# Sheet1.net
KiCad netlist of a schematic drawn in Altium Designer
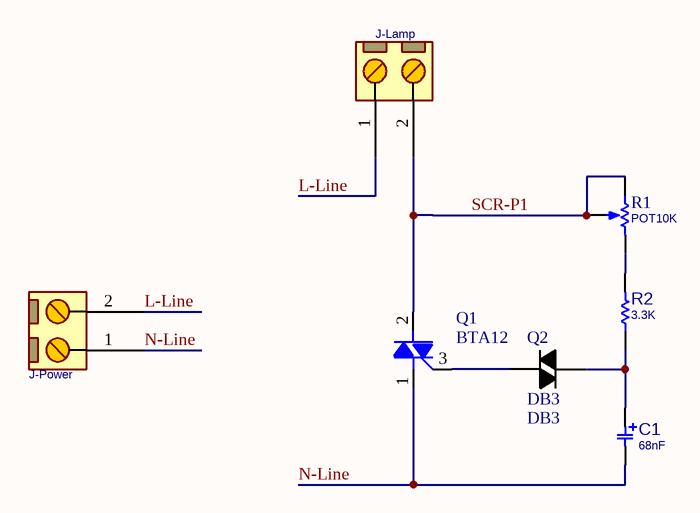
[diagram p0: Sheet1.SchDoc]

(export (version "E")
  (design (tool "Eeschema 10.0.6"))
  (components
    (comp (ref "C1")
      (value "68nF")
      (footprint "C_FLM_7X5H11")
      (description "CAP, THD, FILM,")
      (fields (field (name "MANF_P#") "MANF_PART#") (field (name "MANF") "MANF"))
      (libsource (lib "passive_thd") (part "CAP_THD_FLM"))
    )
    (comp (ref "J-Lamp")
      (value "CONN_TB2")
      (footprint "MSTB_2")
      (description "CONN, PHOENIX MSTB, 5-G, 5.08mm pitch")
      (libsource (lib "conn_terminalB") (part "CONN_MSTB_2"))
    )
    (comp (ref "J-Power")
      (value "CONN_TB2")
      (footprint "MSTB_2")
      (description "CONN, PHOENIX MSTB, 5-G, 5.08mm pitch")
      (libsource (lib "") (part "CONN_MSTB_2_1"))
    )
    (comp (ref "Q1")
      (value "BTA12")
      (footprint "TO220_3")
      (description "Triac, 600V, 12A, TO-220")
      (fields (field (name "MANF_P#") "BTA12-600BW, BTA12-600CW, BTA12-600TW") (field (name "MANF") "ST"))
      (libsource (lib "triac_diac") (part "TRIAC_BTA12-600_TO220"))
    )
    (comp (ref "Q2")
      (value "DB3")
      (footprint "D_AX03_DO35")
      (description "Diac, 32VBO, DO-35")
      (fields (field (name "MANF") "ST") (field (name "ALTIUM_VALUE") "DB3"))
      (libsource (lib "triac_diac") (part "DIAC_DB3_DO35"))
    )
    (comp (ref "R1")
      (value "POT10K")
      (footprint "VOL_R")
      (description "RESISTOR, THD, Potentiometer Volume")
      (libsource (lib "resistor_pot_trimmer") (part "RES_THD_POT_VOL"))
    )
    (comp (ref "R2")
      (value "3.3K")
      (footprint "R025W_AX04")
      (description "RESISTOR, THD")
      (fields (field (name "MANF_P#") "RK73H1ETTP4701F") (field (name "MANF") "KOA SPEER"))
      (libsource (lib "passive_thd") (part "RES_THD"))
    )
  )
  (nets
    (net (code "1") (name "/L-Line") (class "Default")
      (node (ref "J-Lamp") (pin "1") (pinfunction "1_1") (pintype "passive"))
      (node (ref "J-Power") (pin "2") (pinfunction "2_2") (pintype "passive"))
    )
    (net (code "2") (name "/N-Line") (class "Default")
      (node (ref "C1") (pin "2") (pinfunction "2_2") (pintype "passive"))
      (node (ref "J-Power") (pin "1") (pinfunction "1_1") (pintype "passive"))
      (node (ref "Q1") (pin "1") (pinfunction "T1_1") (pintype "passive"))
    )
    (net (code "3") (name "/SCR-P1") (class "Default")
      (node (ref "J-Lamp") (pin "2") (pinfunction "2_2") (pintype "passive"))
      (node (ref "Q1") (pin "2") (pinfunction "T2_2") (pintype "passive"))
      (node (ref "R1") (pin "1") (pinfunction "TOP_1") (pintype "passive"))
      (node (ref "R1") (pin "2") (pinfunction "TAP_2") (pintype "passive"))
    )
    (net (code "4") (name "Net-(Q1-G)") (class "Default")
      (node (ref "Q1") (pin "3") (pinfunction "G_3") (pintype "passive"))
      (node (ref "Q2") (pin "1") (pinfunction "A1_1") (pintype "passive"))
    )
    (net (code "5") (name "Net-(Q2-A2)") (class "Default")
      (node (ref "C1") (pin "1") (pinfunction "1_1") (pintype "passive"))
      (node (ref "Q2") (pin "2") (pinfunction "A2_2") (pintype "passive"))
      (node (ref "R2") (pin "1") (pinfunction "1_1") (pintype "passive"))
    )
    (net (code "6") (name "Net-(R1-BOT)") (class "Default")
      (node (ref "R1") (pin "3") (pinfunction "BOT_3") (pintype "passive"))
      (node (ref "R2") (pin "2") (pinfunction "2_2") (pintype "passive"))
    )
  )
)
